# GERMO.net
KiCad netlist of a schematic drawn in EAGLE
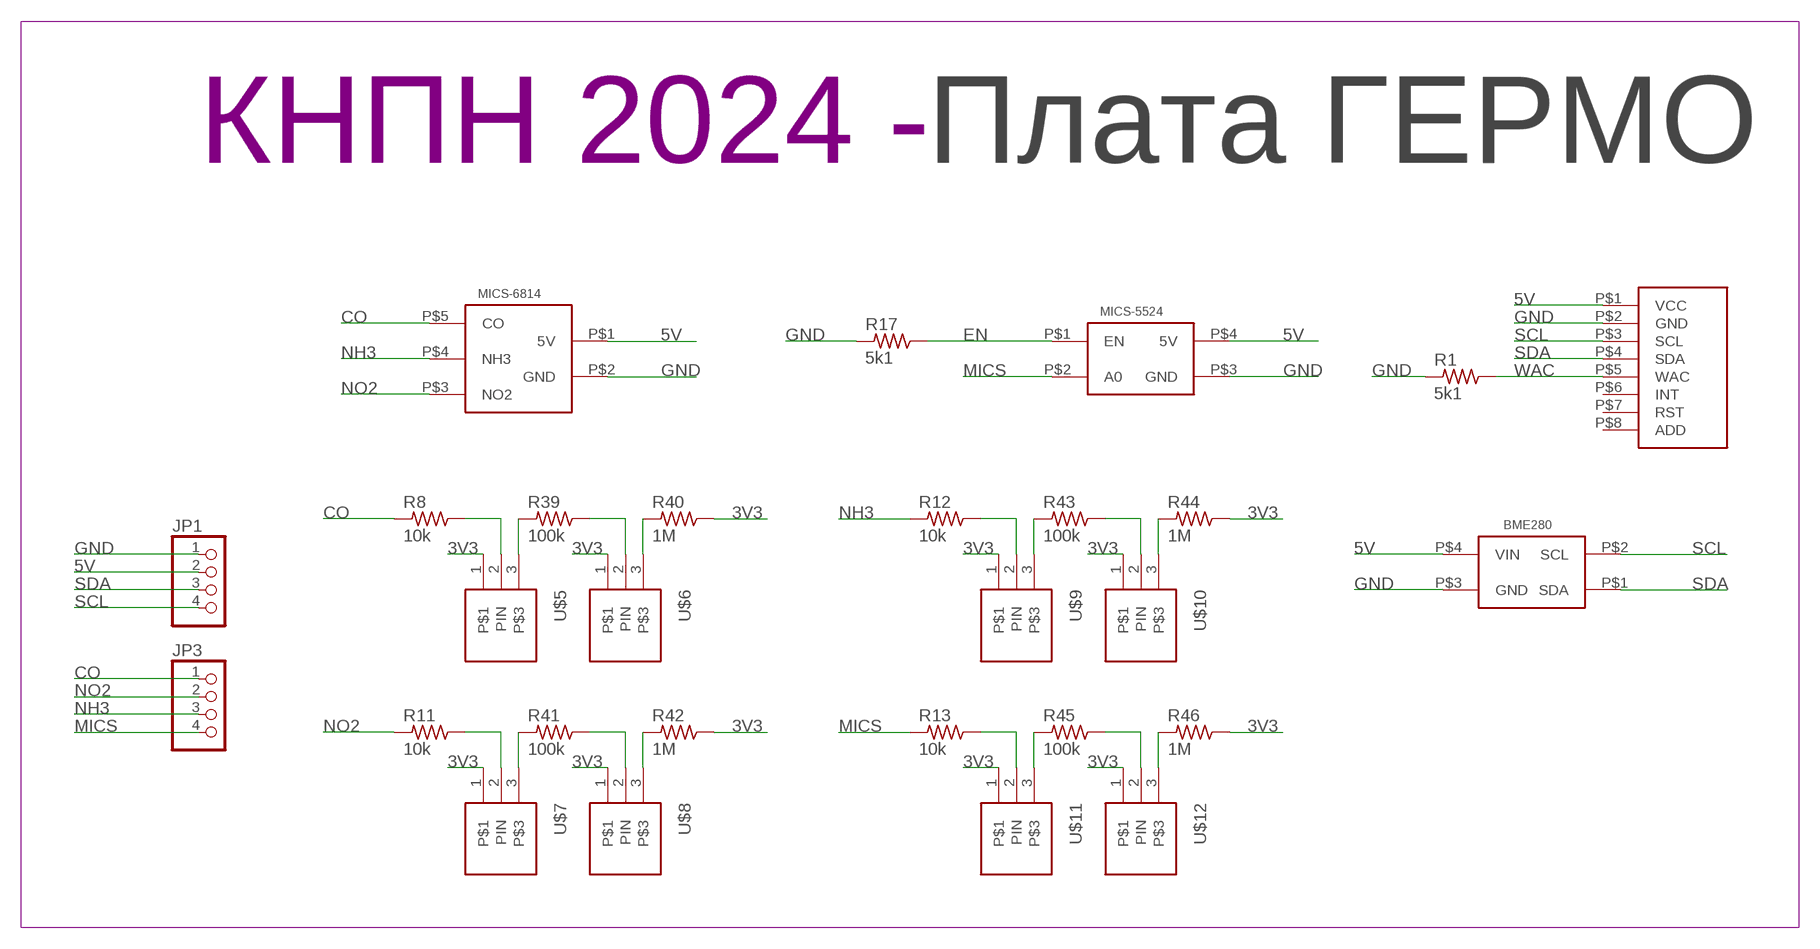
[diagram p0: schematic, sheet 1]

(export (version "E")
  (design (tool "Eeschema 10.0.6"))
  (components
    (comp (ref "BME280")
      (value "BME280BME280-PINS-ONLY")
      (footprint "eagle-import:BME280-PINS-ONLY")
      (libsource (lib "eagle-import") (part "BME280BME280-PINS-ONLY"))
    )
    (comp (ref "JP1")
      (value "PINHD-1X4")
      (footprint "eagle-import:1X04")
      (libsource (lib "eagle-import") (part "PINHD-1X4"))
    )
    (comp (ref "JP3")
      (value "PINHD-1X4")
      (footprint "eagle-import:1X04")
      (libsource (lib "eagle-import") (part "PINHD-1X4"))
    )
    (comp (ref "MICS-5524")
      (value "MICS_5524")
      (footprint "eagle-import:MICS-5524")
      (libsource (lib "eagle-import") (part "MICS_5524"))
    )
    (comp (ref "MICS-6814")
      (value "MICS-6814")
      (footprint "eagle-import:MICS-6814")
      (libsource (lib "eagle-import") (part "MICS-6814"))
    )
    (comp (ref "R1")
      (value "5k1")
      (footprint "eagle-import:R0603")
      (libsource (lib "eagle-import") (part "R-US_R0603"))
    )
    (comp (ref "R8")
      (value "10k")
      (footprint "eagle-import:R0603")
      (libsource (lib "eagle-import") (part "R-US_R0603"))
    )
    (comp (ref "R11")
      (value "10k")
      (footprint "eagle-import:R0603")
      (libsource (lib "eagle-import") (part "R-US_R0603"))
    )
    (comp (ref "R12")
      (value "10k")
      (footprint "eagle-import:R0603")
      (libsource (lib "eagle-import") (part "R-US_R0603"))
    )
    (comp (ref "R13")
      (value "10k")
      (footprint "eagle-import:R0603")
      (libsource (lib "eagle-import") (part "R-US_R0603"))
    )
    (comp (ref "R17")
      (value "5k1")
      (footprint "eagle-import:R0603")
      (libsource (lib "eagle-import") (part "R-US_R0603"))
    )
    (comp (ref "R39")
      (value "100k")
      (footprint "eagle-import:R0603")
      (libsource (lib "eagle-import") (part "R-US_R0603"))
    )
    (comp (ref "R40")
      (value "1M")
      (footprint "eagle-import:R0603")
      (libsource (lib "eagle-import") (part "R-US_R0603"))
    )
    (comp (ref "R41")
      (value "100k")
      (footprint "eagle-import:R0603")
      (libsource (lib "eagle-import") (part "R-US_R0603"))
    )
    (comp (ref "R42")
      (value "1M")
      (footprint "eagle-import:R0603")
      (libsource (lib "eagle-import") (part "R-US_R0603"))
    )
    (comp (ref "R43")
      (value "100k")
      (footprint "eagle-import:R0603")
      (libsource (lib "eagle-import") (part "R-US_R0603"))
    )
    (comp (ref "R44")
      (value "1M")
      (footprint "eagle-import:R0603")
      (libsource (lib "eagle-import") (part "R-US_R0603"))
    )
    (comp (ref "R45")
      (value "100k")
      (footprint "eagle-import:R0603")
      (libsource (lib "eagle-import") (part "R-US_R0603"))
    )
    (comp (ref "R46")
      (value "1M")
      (footprint "eagle-import:R0603")
      (libsource (lib "eagle-import") (part "R-US_R0603"))
    )
    (comp (ref "U$2")
      (value "Плата ГЕРМО")
      (footprint "eagle-import:LOGO")
      (libsource (lib "eagle-import") (part "LOGOPCB-{dblquote}{dblquote}"))
    )
    (comp (ref "U$4")
      (value "CCS811")
      (footprint "eagle-import:CSS811")
      (libsource (lib "eagle-import") (part "CCS811"))
    )
    (comp (ref "U$5")
      (value "CONNECT_3")
      (footprint "eagle-import:CONNECT_3")
      (libsource (lib "eagle-import") (part "CONNECT_3"))
    )
    (comp (ref "U$6")
      (value "CONNECT_3")
      (footprint "eagle-import:CONNECT_3")
      (libsource (lib "eagle-import") (part "CONNECT_3"))
    )
    (comp (ref "U$7")
      (value "CONNECT_3")
      (footprint "eagle-import:CONNECT_3")
      (libsource (lib "eagle-import") (part "CONNECT_3"))
    )
    (comp (ref "U$8")
      (value "CONNECT_3")
      (footprint "eagle-import:CONNECT_3")
      (libsource (lib "eagle-import") (part "CONNECT_3"))
    )
    (comp (ref "U$9")
      (value "CONNECT_3")
      (footprint "eagle-import:CONNECT_3")
      (libsource (lib "eagle-import") (part "CONNECT_3"))
    )
    (comp (ref "U$10")
      (value "CONNECT_3")
      (footprint "eagle-import:CONNECT_3")
      (libsource (lib "eagle-import") (part "CONNECT_3"))
    )
    (comp (ref "U$11")
      (value "CONNECT_3")
      (footprint "eagle-import:CONNECT_3")
      (libsource (lib "eagle-import") (part "CONNECT_3"))
    )
    (comp (ref "U$12")
      (value "CONNECT_3")
      (footprint "eagle-import:CONNECT_3")
      (libsource (lib "eagle-import") (part "CONNECT_3"))
    )
  )
  (nets
    (net (code "1") (name "/3V3") (class "Default")
      (node (ref "R40") (pin "1") (pinfunction "1_1") (pintype "passive"))
      (node (ref "R42") (pin "1") (pinfunction "1_1") (pintype "passive"))
      (node (ref "R44") (pin "1") (pinfunction "1_1") (pintype "passive"))
      (node (ref "R46") (pin "1") (pinfunction "1_1") (pintype "passive"))
      (node (ref "U$10") (pin "1") (pinfunction "P$1_1") (pintype "bidirectional"))
      (node (ref "U$11") (pin "1") (pinfunction "P$1_1") (pintype "bidirectional"))
      (node (ref "U$12") (pin "1") (pinfunction "P$1_1") (pintype "bidirectional"))
      (node (ref "U$5") (pin "1") (pinfunction "P$1_1") (pintype "bidirectional"))
      (node (ref "U$6") (pin "1") (pinfunction "P$1_1") (pintype "bidirectional"))
      (node (ref "U$7") (pin "1") (pinfunction "P$1_1") (pintype "bidirectional"))
      (node (ref "U$8") (pin "1") (pinfunction "P$1_1") (pintype "bidirectional"))
      (node (ref "U$9") (pin "1") (pinfunction "P$1_1") (pintype "bidirectional"))
    )
    (net (code "2") (name "/5V") (class "Default")
      (node (ref "BME280") (pin "P$4") (pinfunction "VIN_P$4") (pintype "bidirectional"))
      (node (ref "JP1") (pin "2") (pinfunction "2_2") (pintype "passive"))
      (node (ref "MICS-5524") (pin "P$4") (pinfunction "5V_P$4") (pintype "bidirectional"))
      (node (ref "MICS-6814") (pin "P$1") (pinfunction "5V_P$1") (pintype "bidirectional"))
      (node (ref "U$4") (pin "P$1") (pinfunction "VCC_P$1") (pintype "bidirectional"))
    )
    (net (code "3") (name "/CO") (class "Default")
      (node (ref "JP3") (pin "1") (pinfunction "1_1") (pintype "passive"))
      (node (ref "MICS-6814") (pin "P$5") (pinfunction "CO_P$5") (pintype "bidirectional"))
      (node (ref "R8") (pin "2") (pinfunction "2_2") (pintype "passive"))
    )
    (net (code "4") (name "/EN") (class "Default")
      (node (ref "MICS-5524") (pin "P$1") (pinfunction "EN_P$1") (pintype "bidirectional"))
      (node (ref "R17") (pin "1") (pinfunction "1_1") (pintype "passive"))
    )
    (net (code "5") (name "/GND") (class "Default")
      (node (ref "BME280") (pin "P$3") (pinfunction "GND_P$3") (pintype "bidirectional"))
      (node (ref "JP1") (pin "1") (pinfunction "1_1") (pintype "passive"))
      (node (ref "MICS-5524") (pin "P$3") (pinfunction "GND_P$3") (pintype "bidirectional"))
      (node (ref "MICS-6814") (pin "P$2") (pinfunction "GND_P$2") (pintype "bidirectional"))
      (node (ref "R1") (pin "2") (pinfunction "2_2") (pintype "passive"))
      (node (ref "R17") (pin "2") (pinfunction "2_2") (pintype "passive"))
      (node (ref "U$4") (pin "P$2") (pinfunction "GND_P$2") (pintype "bidirectional"))
    )
    (net (code "6") (name "/MICS") (class "Default")
      (node (ref "JP3") (pin "4") (pinfunction "4_4") (pintype "passive"))
      (node (ref "MICS-5524") (pin "P$2") (pinfunction "A0_P$2") (pintype "bidirectional"))
      (node (ref "R13") (pin "2") (pinfunction "2_2") (pintype "passive"))
    )
    (net (code "7") (name "/NH3") (class "Default")
      (node (ref "JP3") (pin "3") (pinfunction "3_3") (pintype "passive"))
      (node (ref "MICS-6814") (pin "P$4") (pinfunction "NH3_P$4") (pintype "bidirectional"))
      (node (ref "R12") (pin "2") (pinfunction "2_2") (pintype "passive"))
    )
    (net (code "8") (name "/NO2") (class "Default")
      (node (ref "JP3") (pin "2") (pinfunction "2_2") (pintype "passive"))
      (node (ref "MICS-6814") (pin "P$3") (pinfunction "NO2_P$3") (pintype "bidirectional"))
      (node (ref "R11") (pin "2") (pinfunction "2_2") (pintype "passive"))
    )
    (net (code "9") (name "/SCL") (class "Default")
      (node (ref "BME280") (pin "P$2") (pinfunction "SCL_P$2") (pintype "bidirectional"))
      (node (ref "JP1") (pin "4") (pinfunction "4_4") (pintype "passive"))
      (node (ref "U$4") (pin "P$3") (pinfunction "SCL_P$3") (pintype "bidirectional"))
    )
    (net (code "10") (name "/SDA") (class "Default")
      (node (ref "BME280") (pin "P$1") (pinfunction "SDA_P$1") (pintype "bidirectional"))
      (node (ref "JP1") (pin "3") (pinfunction "3_3") (pintype "passive"))
      (node (ref "U$4") (pin "P$4") (pinfunction "SDA_P$4") (pintype "bidirectional"))
    )
    (net (code "11") (name "/WAC") (class "Default")
      (node (ref "R1") (pin "1") (pinfunction "1_1") (pintype "passive"))
      (node (ref "U$4") (pin "P$5") (pinfunction "WAC_P$5") (pintype "bidirectional"))
    )
    (net (code "12") (name "Net-(U$5-P$3)") (class "Default")
      (node (ref "R39") (pin "2") (pinfunction "2_2") (pintype "passive"))
      (node (ref "U$5") (pin "3") (pinfunction "P$3_3") (pintype "bidirectional"))
    )
    (net (code "13") (name "Net-(U$5-PIN)") (class "Default")
      (node (ref "R8") (pin "1") (pinfunction "1_1") (pintype "passive"))
      (node (ref "U$5") (pin "2") (pinfunction "PIN_2") (pintype "bidirectional"))
    )
    (net (code "14") (name "Net-(U$6-P$3)") (class "Default")
      (node (ref "R40") (pin "2") (pinfunction "2_2") (pintype "passive"))
      (node (ref "U$6") (pin "3") (pinfunction "P$3_3") (pintype "bidirectional"))
    )
    (net (code "15") (name "Net-(U$6-PIN)") (class "Default")
      (node (ref "R39") (pin "1") (pinfunction "1_1") (pintype "passive"))
      (node (ref "U$6") (pin "2") (pinfunction "PIN_2") (pintype "bidirectional"))
    )
    (net (code "16") (name "Net-(U$7-P$3)") (class "Default")
      (node (ref "R41") (pin "2") (pinfunction "2_2") (pintype "passive"))
      (node (ref "U$7") (pin "3") (pinfunction "P$3_3") (pintype "bidirectional"))
    )
    (net (code "17") (name "Net-(U$7-PIN)") (class "Default")
      (node (ref "R11") (pin "1") (pinfunction "1_1") (pintype "passive"))
      (node (ref "U$7") (pin "2") (pinfunction "PIN_2") (pintype "bidirectional"))
    )
    (net (code "18") (name "Net-(U$8-P$3)") (class "Default")
      (node (ref "R42") (pin "2") (pinfunction "2_2") (pintype "passive"))
      (node (ref "U$8") (pin "3") (pinfunction "P$3_3") (pintype "bidirectional"))
    )
    (net (code "19") (name "Net-(U$8-PIN)") (class "Default")
      (node (ref "R41") (pin "1") (pinfunction "1_1") (pintype "passive"))
      (node (ref "U$8") (pin "2") (pinfunction "PIN_2") (pintype "bidirectional"))
    )
    (net (code "20") (name "Net-(U$9-P$3)") (class "Default")
      (node (ref "R43") (pin "2") (pinfunction "2_2") (pintype "passive"))
      (node (ref "U$9") (pin "3") (pinfunction "P$3_3") (pintype "bidirectional"))
    )
    (net (code "21") (name "Net-(U$9-PIN)") (class "Default")
      (node (ref "R12") (pin "1") (pinfunction "1_1") (pintype "passive"))
      (node (ref "U$9") (pin "2") (pinfunction "PIN_2") (pintype "bidirectional"))
    )
    (net (code "22") (name "Net-(U$10-P$3)") (class "Default")
      (node (ref "R44") (pin "2") (pinfunction "2_2") (pintype "passive"))
      (node (ref "U$10") (pin "3") (pinfunction "P$3_3") (pintype "bidirectional"))
    )
    (net (code "23") (name "Net-(U$10-PIN)") (class "Default")
      (node (ref "R43") (pin "1") (pinfunction "1_1") (pintype "passive"))
      (node (ref "U$10") (pin "2") (pinfunction "PIN_2") (pintype "bidirectional"))
    )
    (net (code "24") (name "Net-(U$11-P$3)") (class "Default")
      (node (ref "R45") (pin "2") (pinfunction "2_2") (pintype "passive"))
      (node (ref "U$11") (pin "3") (pinfunction "P$3_3") (pintype "bidirectional"))
    )
    (net (code "25") (name "Net-(U$11-PIN)") (class "Default")
      (node (ref "R13") (pin "1") (pinfunction "1_1") (pintype "passive"))
      (node (ref "U$11") (pin "2") (pinfunction "PIN_2") (pintype "bidirectional"))
    )
    (net (code "26") (name "Net-(U$12-P$3)") (class "Default")
      (node (ref "R46") (pin "2") (pinfunction "2_2") (pintype "passive"))
      (node (ref "U$12") (pin "3") (pinfunction "P$3_3") (pintype "bidirectional"))
    )
    (net (code "27") (name "Net-(U$12-PIN)") (class "Default")
      (node (ref "R45") (pin "1") (pinfunction "1_1") (pintype "passive"))
      (node (ref "U$12") (pin "2") (pinfunction "PIN_2") (pintype "bidirectional"))
    )
    (net (code "28") (name "unconnected-(U$4-ADD-PadP$8)") (class "Default")
      (node (ref "U$4") (pin "P$8") (pinfunction "ADD_P$8") (pintype "bidirectional"))
    )
    (net (code "29") (name "unconnected-(U$4-INT-PadP$6)") (class "Default")
      (node (ref "U$4") (pin "P$6") (pinfunction "INT_P$6") (pintype "bidirectional"))
    )
    (net (code "30") (name "unconnected-(U$4-RST-PadP$7)") (class "Default")
      (node (ref "U$4") (pin "P$7") (pinfunction "RST_P$7") (pintype "bidirectional"))
    )
  )
)
